# FSR402.net
KiCad netlist of a schematic drawn in EasyEDA Pro
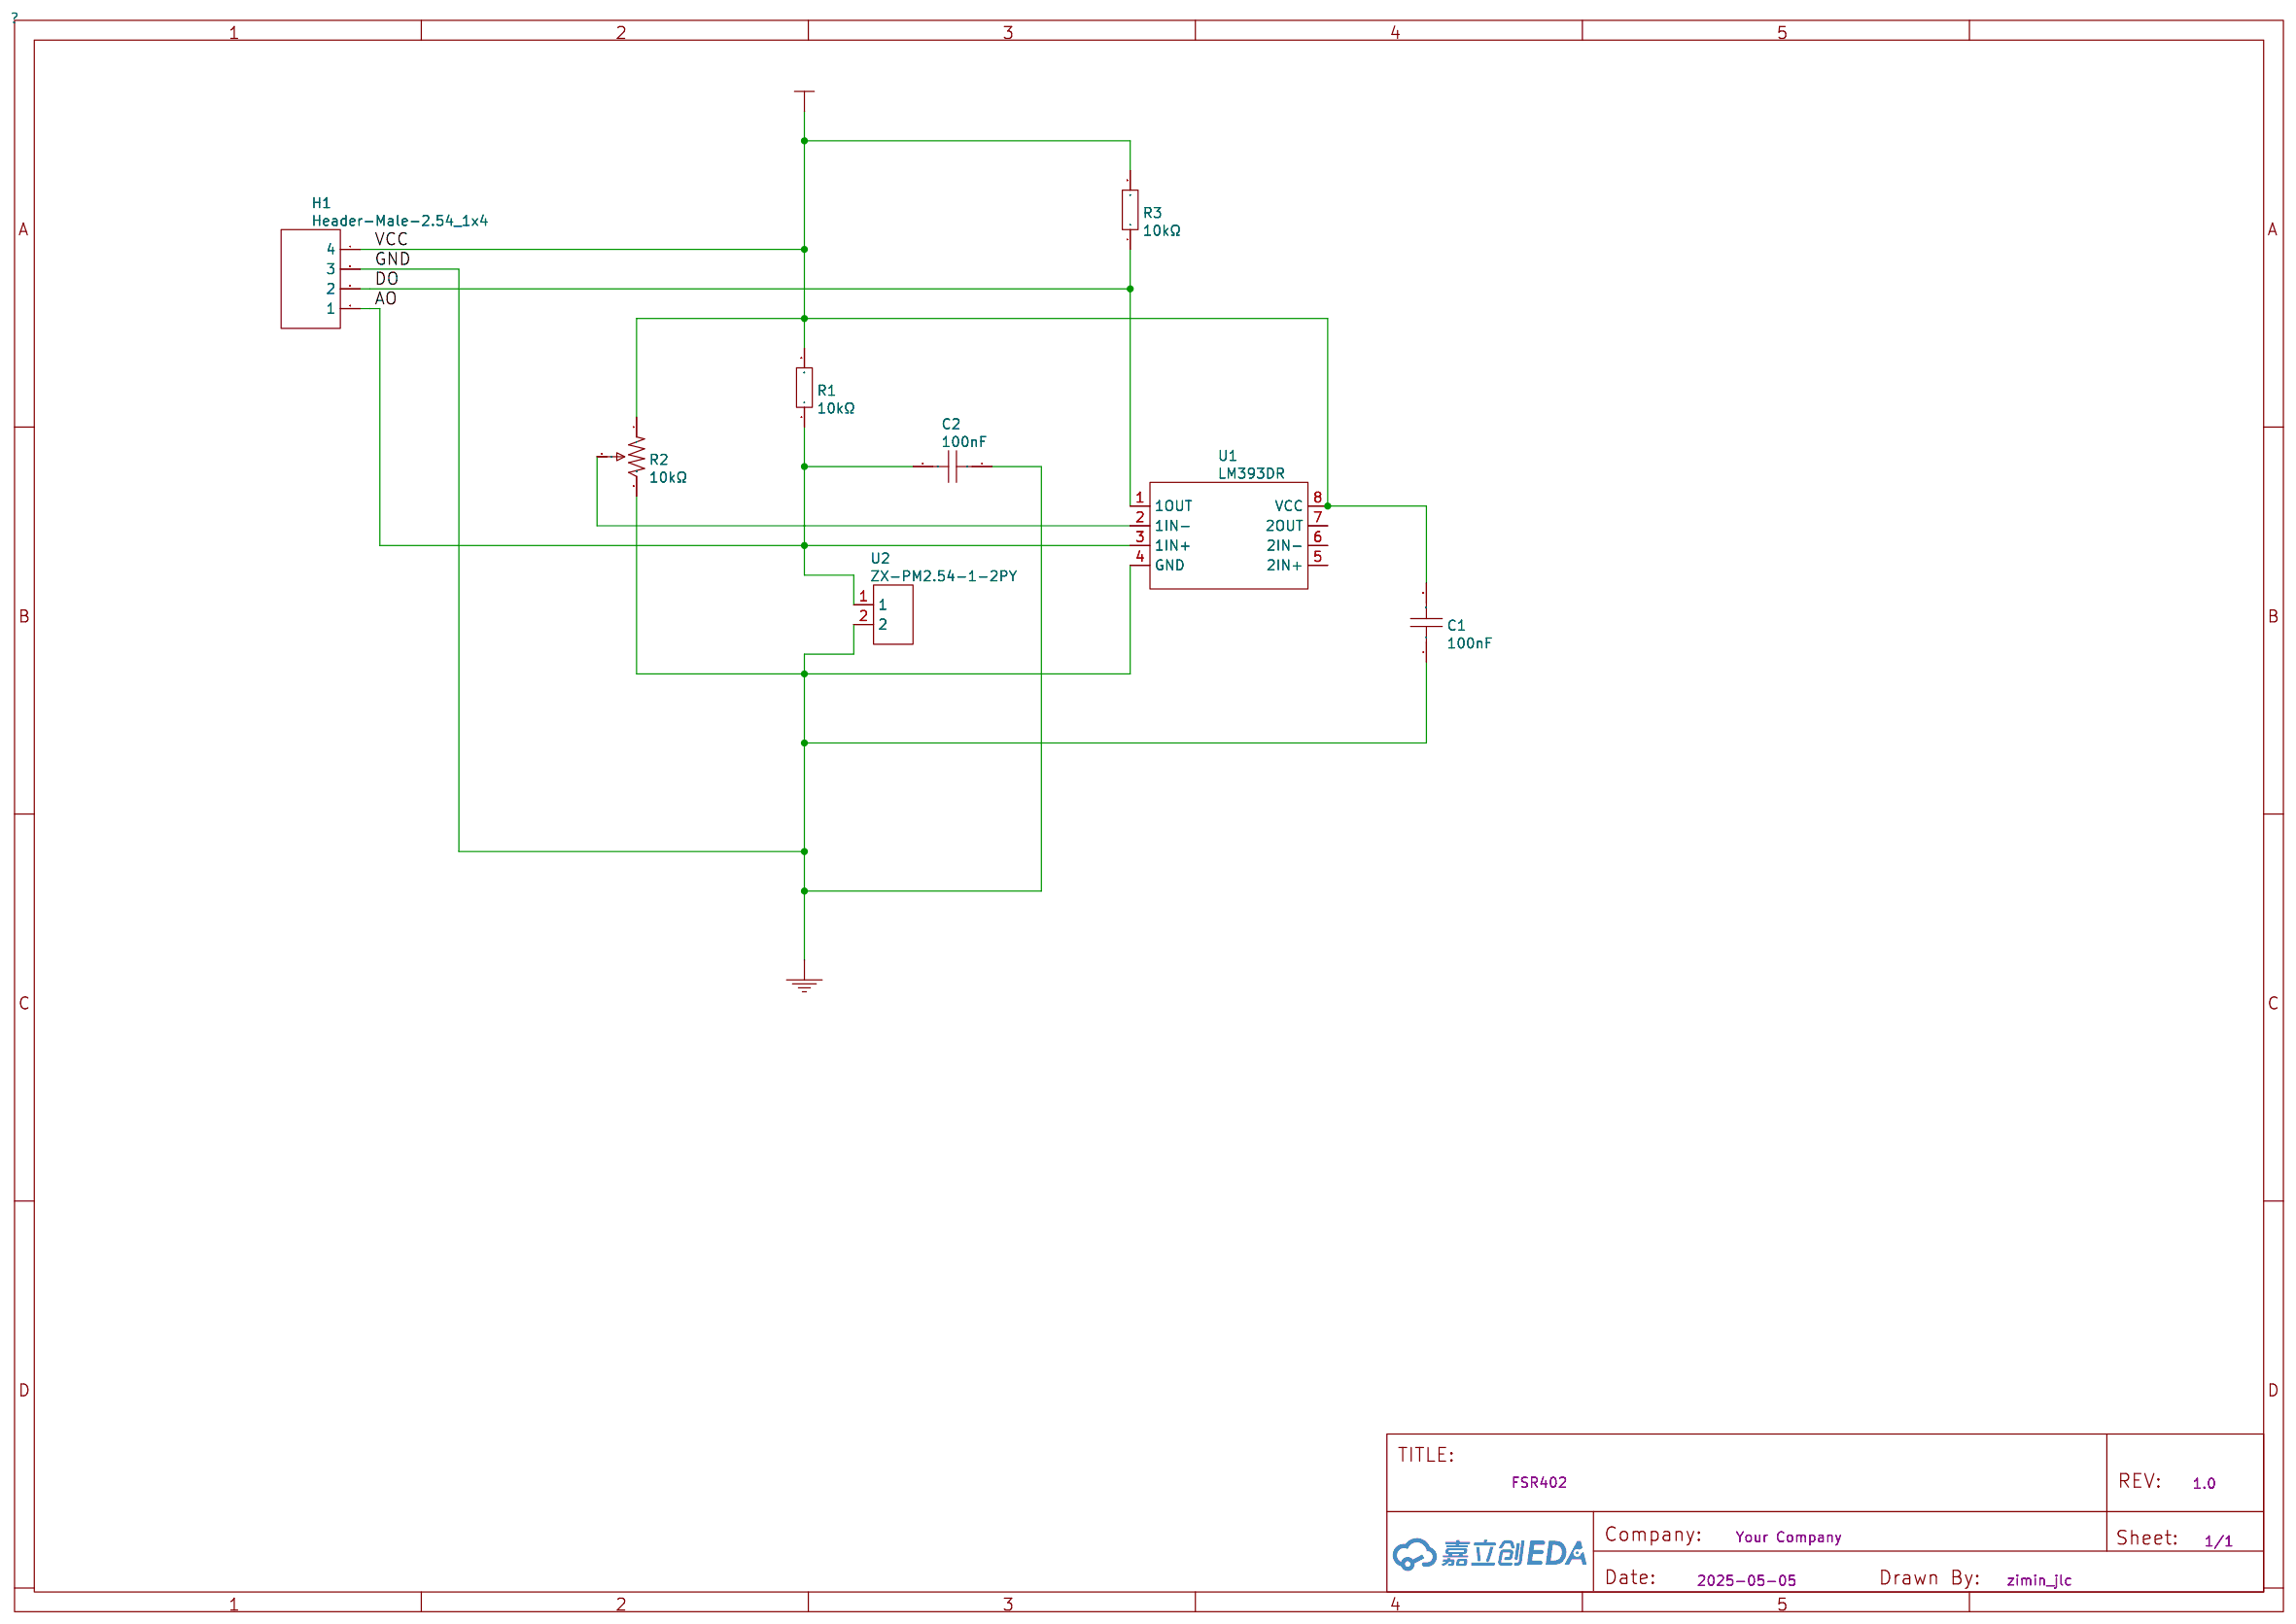
[diagram p0: schematic sheet]

(export (version "E")
  (design (tool "Eeschema 10.0.6"))
  (components
    (comp (ref "C1")
      (value "100nF")
      (footprint "easyedapro:C0603")
      (fields
        (field (name "Manufacturer Part") "CGA0603X7R104K500JT")
        (field (name "Manufacturer") "HRE(芯声)")
        (field (name "Contributor") "lcsc")
      )
      (libsource (lib "easyedapro") (part "100nF"))
    )
    (comp (ref "C2")
      (value "100nF")
      (footprint "easyedapro:C0603")
      (fields
        (field (name "Manufacturer Part") "CGA0603X7R104K500JT")
        (field (name "Manufacturer") "HRE(芯声)")
        (field (name "Contributor") "lcsc")
      )
      (libsource (lib "easyedapro") (part "100nF"))
    )
    (comp (ref "H1")
      (value "Header-Male-2.54_1x4")
      (footprint "easyedapro:HDR-TH_4P-P2.54-V-M")
      (fields
        (field (name "Manufacturer Part") "B-2100S04P-A110")
        (field (name "Manufacturer") "Ckmtw(灿科盟)")
        (field (name "Contributor") "LCSC")
      )
      (libsource (lib "easyedapro") (part "Header-Male-2.54_1x4"))
    )
    (comp (ref "R1")
      (value "10kΩ")
      (footprint "easyedapro:R0603")
      (fields
        (field (name "Manufacturer Part") "0603WAF1002T5E")
        (field (name "Manufacturer") "UNI-ROYAL(厚声)")
      )
      (libsource (lib "easyedapro") (part "10kΩ"))
    )
    (comp (ref "R2")
      (value "10kΩ")
      (footprint "easyedapro:RES-ADJ-TH_3362P")
      (fields
        (field (name "Manufacturer Part") "3362P-1-103")
        (field (name "Manufacturer") "BOCHEN(博晨)")
        (field (name "Contributor") "LCSC")
      )
      (libsource (lib "") (part "10kΩ_1"))
    )
    (comp (ref "R3")
      (value "10kΩ")
      (footprint "easyedapro:R0603")
      (fields
        (field (name "Manufacturer Part") "0603WAF1002T5E")
        (field (name "Manufacturer") "UNI-ROYAL(厚声)")
      )
      (libsource (lib "easyedapro") (part "10kΩ"))
    )
    (comp (ref "U1")
      (value "LM393DR")
      (footprint "easyedapro:SOIC-8_L5.0-W4.0-P1.27-LS6.0-BL")
      (fields (field (name "Manufacturer") "TI(德州仪器)"))
      (libsource (lib "easyedapro") (part "LM393DR"))
    )
    (comp (ref "U2")
      (value "ZX-PM2.54-1-2PY")
      (footprint "easyedapro:HDR-TH_2P-P2.54-V-F")
      (fields (field (name "Manufacturer") "Megastar(兆星)") (field (name "Contributor") "lcsc"))
      (libsource (lib "easyedapro") (part "ZX-PM2.54-1-2PY"))
    )
  )
  (nets
    (net (code "1") (name "/AO") (class "Default")
      (node (ref "C2") (pin "2") (pinfunction "2_2") (pintype "unspecified"))
      (node (ref "H1") (pin "1") (pinfunction "1_1") (pintype "unspecified"))
      (node (ref "R1") (pin "1") (pinfunction "1_1") (pintype "input"))
      (node (ref "U1") (pin "3") (pinfunction "1IN+_3") (pintype "unspecified"))
      (node (ref "U2") (pin "1") (pinfunction "1_1") (pintype "unspecified"))
    )
    (net (code "2") (name "/DO") (class "Default")
      (node (ref "H1") (pin "2") (pinfunction "2_2") (pintype "unspecified"))
      (node (ref "R3") (pin "1") (pinfunction "1_1") (pintype "input"))
      (node (ref "U1") (pin "1") (pinfunction "1OUT_1") (pintype "unspecified"))
    )
    (net (code "3") (name "GND") (class "Default")
      (node (ref "C1") (pin "1") (pinfunction "1_1") (pintype "unspecified"))
      (node (ref "C2") (pin "1") (pinfunction "1_1") (pintype "unspecified"))
      (node (ref "H1") (pin "3") (pinfunction "3_3") (pintype "unspecified"))
      (node (ref "R2") (pin "3") (pinfunction "3_3") (pintype "unspecified"))
      (node (ref "U1") (pin "4") (pinfunction "GND_4") (pintype "unspecified"))
      (node (ref "U2") (pin "2") (pinfunction "2_2") (pintype "unspecified"))
    )
    (net (code "4") (name "Net-(U1-1IN-)") (class "Default")
      (node (ref "R2") (pin "2") (pinfunction "2_2") (pintype "unspecified"))
      (node (ref "U1") (pin "2") (pinfunction "1IN-_2") (pintype "unspecified"))
    )
    (net (code "5") (name "VCC") (class "Default")
      (node (ref "C1") (pin "2") (pinfunction "2_2") (pintype "unspecified"))
      (node (ref "H1") (pin "4") (pinfunction "4_4") (pintype "unspecified"))
      (node (ref "R1") (pin "2") (pinfunction "2_2") (pintype "input"))
      (node (ref "R2") (pin "1") (pinfunction "1_1") (pintype "unspecified"))
      (node (ref "R3") (pin "2") (pinfunction "2_2") (pintype "input"))
      (node (ref "U1") (pin "8") (pinfunction "VCC_8") (pintype "unspecified"))
    )
    (net (code "6") (name "unconnected-(U1-2IN+-Pad5)") (class "Default")
      (node (ref "U1") (pin "5") (pinfunction "2IN+_5") (pintype "unspecified"))
    )
    (net (code "7") (name "unconnected-(U1-2IN--Pad6)") (class "Default")
      (node (ref "U1") (pin "6") (pinfunction "2IN-_6") (pintype "unspecified"))
    )
    (net (code "8") (name "unconnected-(U1-2OUT-Pad7)") (class "Default")
      (node (ref "U1") (pin "7") (pinfunction "2OUT_7") (pintype "unspecified"))
    )
  )
)
